# 06-Si5341_PLL.net
KiCad netlist of a schematic drawn in Altium Designer
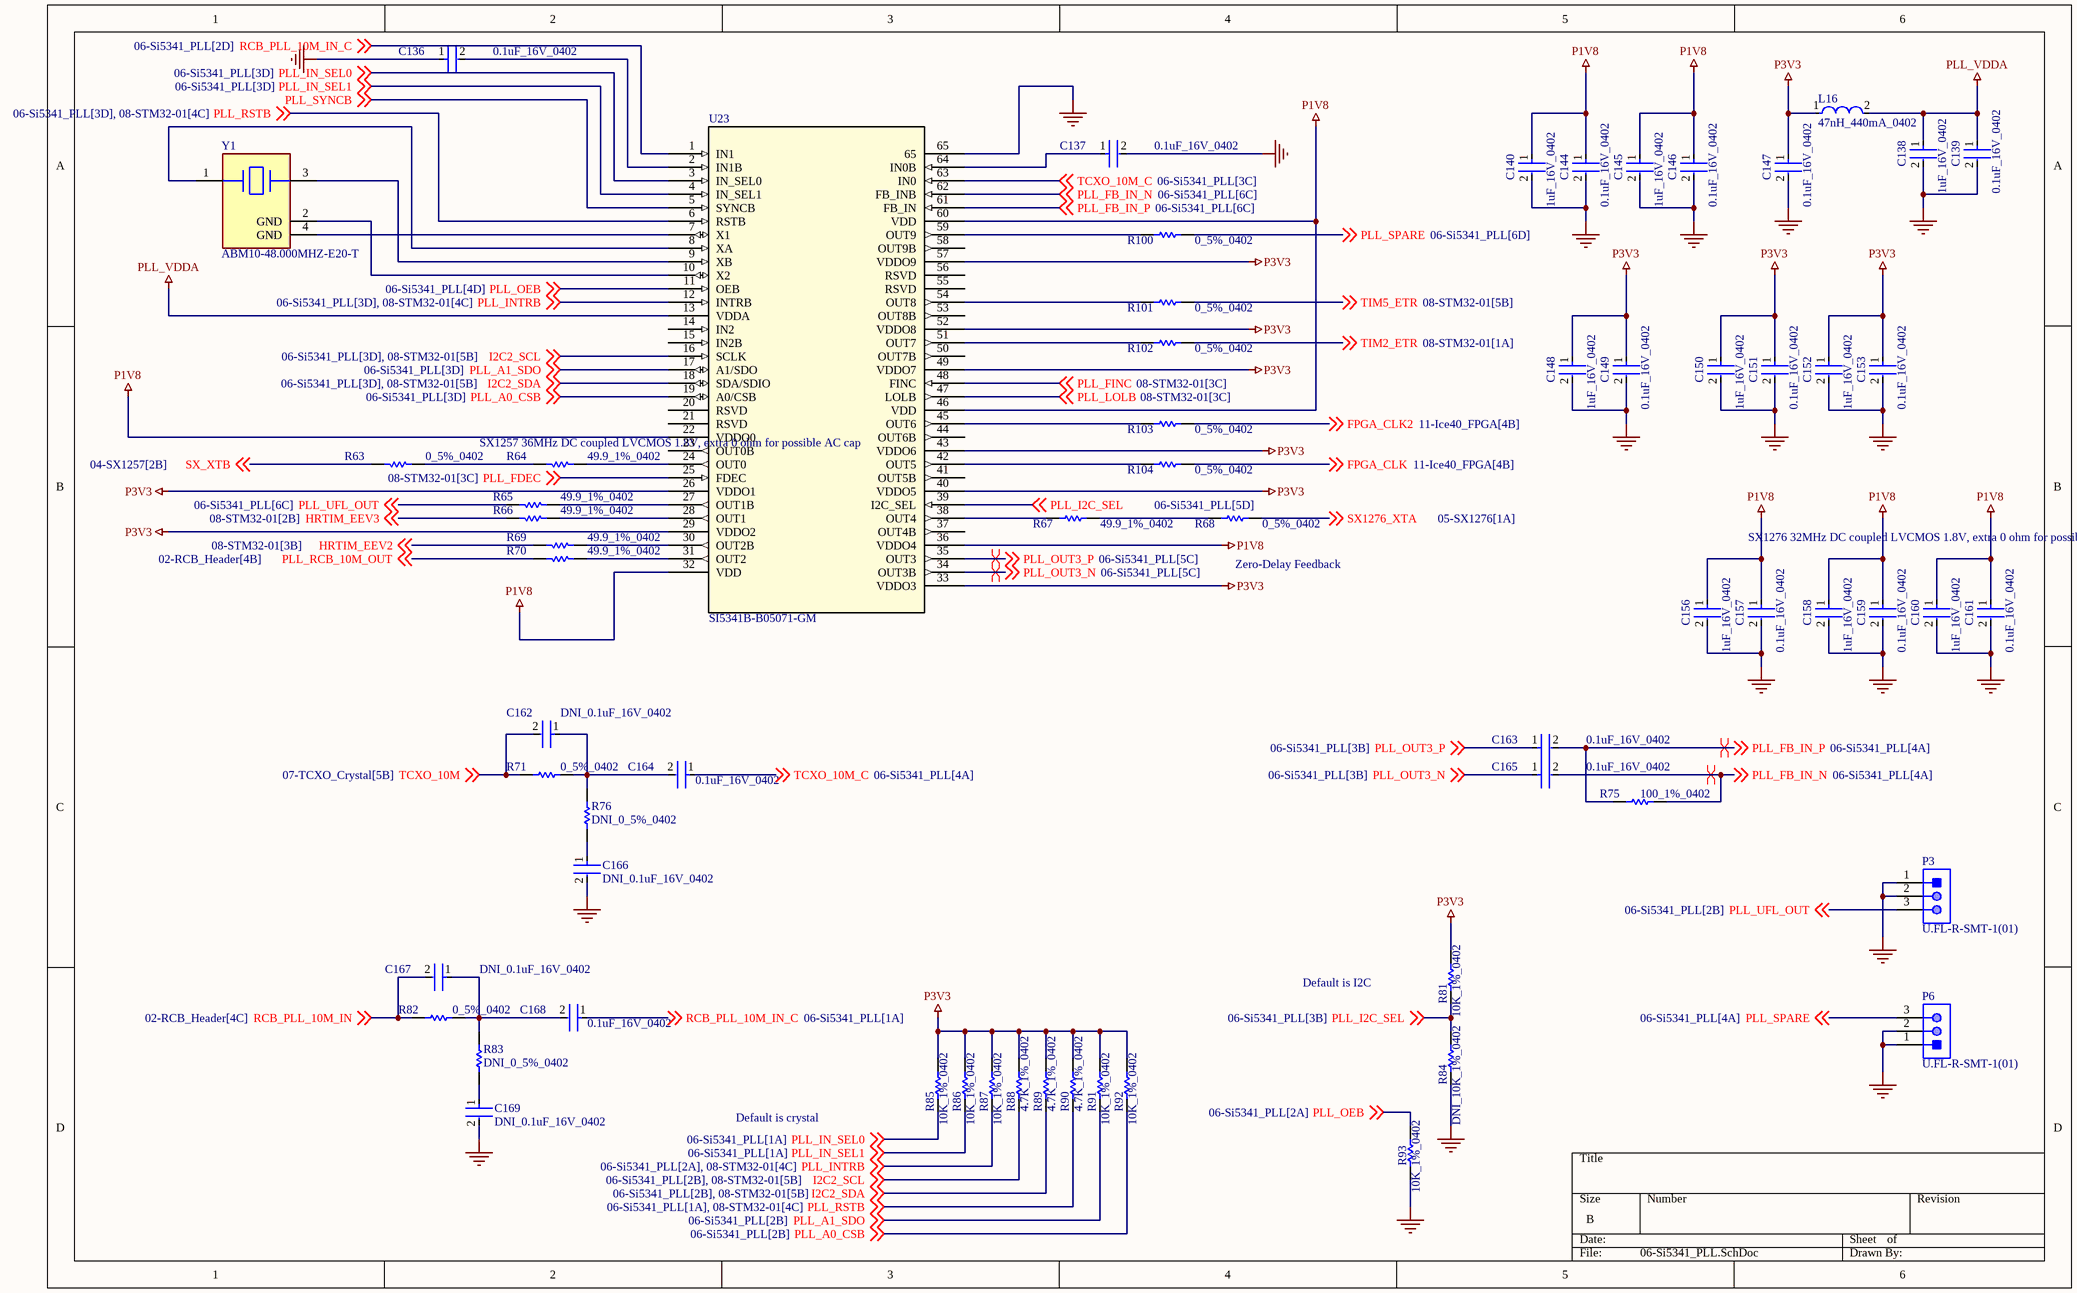
[diagram p0: 06-Si5341_PLL.SchDoc]

(export (version "E")
  (design (tool "Eeschema 10.0.6"))
  (components
    (comp (ref "C136")
      (value "0.1uF_16V_0402")
      (footprint "FP-C0402-BB-MFG")
      (description "CAP CER 0.1UF 16V 5% X7R 0402")
      (fields
        (field (name "MANUFACTURER") "Kemet")
        (field (name "MANUFACTURER PART NUMBER") "C0402C104J4RACTU")
      )
      (libsource (lib "Altium Content Vault") (part "b4654b650e69147ec39a6b967a45e02"))
    )
    (comp (ref "C137")
      (value "0.1uF_16V_0402")
      (footprint "FP-C0402-BB-MFG")
      (description "CAP CER 0.1UF 16V 5% X7R 0402")
      (fields
        (field (name "MANUFACTURER") "Kemet")
        (field (name "MANUFACTURER PART NUMBER") "C0402C104J4RACTU")
      )
      (libsource (lib "Altium Content Vault") (part "b4654b650e69147ec39a6b967a45e02"))
    )
    (comp (ref "C138")
      (value "1uF_16V_0402")
      (footprint "FP-0402-L_1_0_0_05-W_0_5-IPC_A")
      (description "None")
      (fields (field (name "TOLERANCE") "10%"))
      (libsource (lib "Altium Content Vault") (part "b4654b650e69147ec39a6b967a45e02"))
    )
    (comp (ref "C139")
      (value "0.1uF_16V_0402")
      (footprint "FP-C0402-BB-MFG")
      (description "CAP CER 0.1UF 16V 5% X7R 0402")
      (fields
        (field (name "MANUFACTURER") "Kemet")
        (field (name "MANUFACTURER PART NUMBER") "C0402C104J4RACTU")
      )
      (libsource (lib "Altium Content Vault") (part "b4654b650e69147ec39a6b967a45e02"))
    )
    (comp (ref "C140")
      (value "1uF_16V_0402")
      (footprint "FP-0402-L_1_0_0_05-W_0_5-IPC_A")
      (description "None")
      (fields (field (name "TOLERANCE") "10%"))
      (libsource (lib "Altium Content Vault") (part "b4654b650e69147ec39a6b967a45e02"))
    )
    (comp (ref "C144")
      (value "0.1uF_16V_0402")
      (footprint "FP-C0402-BB-MFG")
      (description "CAP CER 0.1UF 16V 5% X7R 0402")
      (fields
        (field (name "MANUFACTURER") "Kemet")
        (field (name "MANUFACTURER PART NUMBER") "C0402C104J4RACTU")
      )
      (libsource (lib "Altium Content Vault") (part "b4654b650e69147ec39a6b967a45e02"))
    )
    (comp (ref "C145")
      (value "1uF_16V_0402")
      (footprint "FP-0402-L_1_0_0_05-W_0_5-IPC_A")
      (description "None")
      (fields (field (name "TOLERANCE") "10%"))
      (libsource (lib "Altium Content Vault") (part "b4654b650e69147ec39a6b967a45e02"))
    )
    (comp (ref "C146")
      (value "0.1uF_16V_0402")
      (footprint "FP-C0402-BB-MFG")
      (description "CAP CER 0.1UF 16V 5% X7R 0402")
      (fields
        (field (name "MANUFACTURER") "Kemet")
        (field (name "MANUFACTURER PART NUMBER") "C0402C104J4RACTU")
      )
      (libsource (lib "Altium Content Vault") (part "b4654b650e69147ec39a6b967a45e02"))
    )
    (comp (ref "C147")
      (value "0.1uF_16V_0402")
      (footprint "FP-C0402-BB-MFG")
      (description "CAP CER 0.1UF 16V 5% X7R 0402")
      (fields
        (field (name "MANUFACTURER") "Kemet")
        (field (name "MANUFACTURER PART NUMBER") "C0402C104J4RACTU")
      )
      (libsource (lib "Altium Content Vault") (part "b4654b650e69147ec39a6b967a45e02"))
    )
    (comp (ref "C148")
      (value "1uF_16V_0402")
      (footprint "FP-0402-L_1_0_0_05-W_0_5-IPC_A")
      (description "None")
      (fields (field (name "TOLERANCE") "10%"))
      (libsource (lib "Altium Content Vault") (part "b4654b650e69147ec39a6b967a45e02"))
    )
    (comp (ref "C149")
      (value "0.1uF_16V_0402")
      (footprint "FP-C0402-BB-MFG")
      (description "CAP CER 0.1UF 16V 5% X7R 0402")
      (fields
        (field (name "MANUFACTURER") "Kemet")
        (field (name "MANUFACTURER PART NUMBER") "C0402C104J4RACTU")
      )
      (libsource (lib "Altium Content Vault") (part "b4654b650e69147ec39a6b967a45e02"))
    )
    (comp (ref "C150")
      (value "1uF_16V_0402")
      (footprint "FP-0402-L_1_0_0_05-W_0_5-IPC_A")
      (description "None")
      (fields (field (name "TOLERANCE") "10%"))
      (libsource (lib "Altium Content Vault") (part "b4654b650e69147ec39a6b967a45e02"))
    )
    (comp (ref "C151")
      (value "0.1uF_16V_0402")
      (footprint "FP-C0402-BB-MFG")
      (description "CAP CER 0.1UF 16V 5% X7R 0402")
      (fields
        (field (name "MANUFACTURER") "Kemet")
        (field (name "MANUFACTURER PART NUMBER") "C0402C104J4RACTU")
      )
      (libsource (lib "Altium Content Vault") (part "b4654b650e69147ec39a6b967a45e02"))
    )
    (comp (ref "C152")
      (value "1uF_16V_0402")
      (footprint "FP-0402-L_1_0_0_05-W_0_5-IPC_A")
      (description "None")
      (fields (field (name "TOLERANCE") "10%"))
      (libsource (lib "Altium Content Vault") (part "b4654b650e69147ec39a6b967a45e02"))
    )
    (comp (ref "C153")
      (value "0.1uF_16V_0402")
      (footprint "FP-C0402-BB-MFG")
      (description "CAP CER 0.1UF 16V 5% X7R 0402")
      (fields
        (field (name "MANUFACTURER") "Kemet")
        (field (name "MANUFACTURER PART NUMBER") "C0402C104J4RACTU")
      )
      (libsource (lib "Altium Content Vault") (part "b4654b650e69147ec39a6b967a45e02"))
    )
    (comp (ref "C156")
      (value "1uF_16V_0402")
      (footprint "FP-0402-L_1_0_0_05-W_0_5-IPC_A")
      (description "None")
      (fields (field (name "TOLERANCE") "10%"))
      (libsource (lib "Altium Content Vault") (part "b4654b650e69147ec39a6b967a45e02"))
    )
    (comp (ref "C157")
      (value "0.1uF_16V_0402")
      (footprint "FP-C0402-BB-MFG")
      (description "CAP CER 0.1UF 16V 5% X7R 0402")
      (fields
        (field (name "MANUFACTURER") "Kemet")
        (field (name "MANUFACTURER PART NUMBER") "C0402C104J4RACTU")
      )
      (libsource (lib "Altium Content Vault") (part "b4654b650e69147ec39a6b967a45e02"))
    )
    (comp (ref "C158")
      (value "1uF_16V_0402")
      (footprint "FP-0402-L_1_0_0_05-W_0_5-IPC_A")
      (description "None")
      (fields (field (name "TOLERANCE") "10%"))
      (libsource (lib "Altium Content Vault") (part "b4654b650e69147ec39a6b967a45e02"))
    )
    (comp (ref "C159")
      (value "0.1uF_16V_0402")
      (footprint "FP-C0402-BB-MFG")
      (description "CAP CER 0.1UF 16V 5% X7R 0402")
      (fields
        (field (name "MANUFACTURER") "Kemet")
        (field (name "MANUFACTURER PART NUMBER") "C0402C104J4RACTU")
      )
      (libsource (lib "Altium Content Vault") (part "b4654b650e69147ec39a6b967a45e02"))
    )
    (comp (ref "C160")
      (value "1uF_16V_0402")
      (footprint "FP-0402-L_1_0_0_05-W_0_5-IPC_A")
      (description "None")
      (fields (field (name "TOLERANCE") "10%"))
      (libsource (lib "Altium Content Vault") (part "b4654b650e69147ec39a6b967a45e02"))
    )
    (comp (ref "C161")
      (value "0.1uF_16V_0402")
      (footprint "FP-C0402-BB-MFG")
      (description "CAP CER 0.1UF 16V 5% X7R 0402")
      (fields
        (field (name "MANUFACTURER") "Kemet")
        (field (name "MANUFACTURER PART NUMBER") "C0402C104J4RACTU")
      )
      (libsource (lib "Altium Content Vault") (part "b4654b650e69147ec39a6b967a45e02"))
    )
    (comp (ref "C162")
      (value "DNI_0.1uF_16V_0402")
      (footprint "FP-C0402-BB-MFG")
      (description "CAP CER 0.1UF 16V 5% X7R 0402")
      (fields
        (field (name "MANUFACTURER") "Kemet")
        (field (name "MANUFACTURER PART NUMBER") "C0402C104J4RACTU")
      )
      (libsource (lib "Altium Content Vault") (part "b4654b650e69147ec39a6b967a45e02"))
    )
    (comp (ref "C163")
      (value "0.1uF_16V_0402")
      (footprint "FP-C0402-BB-MFG")
      (description "CAP CER 0.1UF 16V 5% X7R 0402")
      (fields
        (field (name "MANUFACTURER") "Kemet")
        (field (name "MANUFACTURER PART NUMBER") "C0402C104J4RACTU")
      )
      (libsource (lib "Altium Content Vault") (part "b4654b650e69147ec39a6b967a45e02"))
    )
    (comp (ref "C164")
      (value "0.1uF_16V_0402")
      (footprint "FP-C0402-BB-MFG")
      (description "CAP CER 0.1UF 16V 5% X7R 0402")
      (fields
        (field (name "MANUFACTURER") "Kemet")
        (field (name "MANUFACTURER PART NUMBER") "C0402C104J4RACTU")
      )
      (libsource (lib "Altium Content Vault") (part "b4654b650e69147ec39a6b967a45e02"))
    )
    (comp (ref "C165")
      (value "0.1uF_16V_0402")
      (footprint "FP-C0402-BB-MFG")
      (description "CAP CER 0.1UF 16V 5% X7R 0402")
      (fields
        (field (name "MANUFACTURER") "Kemet")
        (field (name "MANUFACTURER PART NUMBER") "C0402C104J4RACTU")
      )
      (libsource (lib "Altium Content Vault") (part "b4654b650e69147ec39a6b967a45e02"))
    )
    (comp (ref "C166")
      (value "DNI_0.1uF_16V_0402")
      (footprint "FP-C0402-BB-MFG")
      (description "CAP CER 0.1UF 16V 5% X7R 0402")
      (fields
        (field (name "MANUFACTURER") "Kemet")
        (field (name "MANUFACTURER PART NUMBER") "C0402C104J4RACTU")
      )
      (libsource (lib "Altium Content Vault") (part "b4654b650e69147ec39a6b967a45e02"))
    )
    (comp (ref "C167")
      (value "DNI_0.1uF_16V_0402")
      (footprint "FP-C0402-BB-MFG")
      (description "CAP CER 0.1UF 16V 5% X7R 0402")
      (fields
        (field (name "MANUFACTURER") "Kemet")
        (field (name "MANUFACTURER PART NUMBER") "C0402C104J4RACTU")
      )
      (libsource (lib "Altium Content Vault") (part "b4654b650e69147ec39a6b967a45e02"))
    )
    (comp (ref "C168")
      (value "0.1uF_16V_0402")
      (footprint "FP-C0402-BB-MFG")
      (description "CAP CER 0.1UF 16V 5% X7R 0402")
      (fields
        (field (name "MANUFACTURER") "Kemet")
        (field (name "MANUFACTURER PART NUMBER") "C0402C104J4RACTU")
      )
      (libsource (lib "Altium Content Vault") (part "b4654b650e69147ec39a6b967a45e02"))
    )
    (comp (ref "C169")
      (value "DNI_0.1uF_16V_0402")
      (footprint "FP-C0402-BB-MFG")
      (description "CAP CER 0.1UF 16V 5% X7R 0402")
      (fields
        (field (name "MANUFACTURER") "Kemet")
        (field (name "MANUFACTURER PART NUMBER") "C0402C104J4RACTU")
      )
      (libsource (lib "Altium Content Vault") (part "b4654b650e69147ec39a6b967a45e02"))
    )
    (comp (ref "L16")
      (value "47nH_440mA_0402")
      (footprint "FP-LQW15AN_80-MFG")
      (description "Wire Wound RF Inductor 47nH ±5% 440mA 0.648Ω 0402 (1005)")
      (fields (field (name "TOLERANCE") "5%"))
      (libsource (lib "Altium Content Vault") (part "725321dda6339637d4d059423bc1c3c"))
    )
    (comp (ref "P3")
      (value "U.FL-R-SMT-1(01)")
      (footprint "HRS-U.FL-R-SMT-3_V")
      (description "Ultra Small Coaxial Connector, 6 GHz, -40 to 90 degC, 3-Pin SMD, RoHS, Bulk")
      (fields (field (name "MANUFACTURER") "Hirose Electric"))
      (libsource (lib "Altium Content Vault") (part "CN-1P-M-R3"))
    )
    (comp (ref "P6")
      (value "U.FL-R-SMT-1(01)")
      (footprint "HRS-U.FL-R-SMT-3_V")
      (description "Ultra Small Coaxial Connector, 6 GHz, -40 to 90 degC, 3-Pin SMD, RoHS, Bulk")
      (fields (field (name "MANUFACTURER") "Hirose Electric"))
      (libsource (lib "") (part "CN-1P-M-R3_1"))
    )
    (comp (ref "R63")
      (value "0_5%_0402")
      (footprint "RESC1005X40X25NL05T10")
      (fields (field (name "MANUFACTURER") "Panasonic") (field (name "PART NUMBER") "ERJ-U020R00X"))
      (libsource (lib "Altium Content Vault") (part "RES"))
    )
    (comp (ref "R64")
      (value "49.9_1%_0402")
      (footprint "RESC1005X40X25NL10T10")
      (fields (field (name "PART NUMBER") "RK73H1ETTP49R9F") (field (name "MANUFACTURER") "KOA Speer"))
      (libsource (lib "Altium Content Vault") (part "RES"))
    )
    (comp (ref "R65")
      (value "49.9_1%_0402")
      (footprint "RESC1005X40X25NL10T10")
      (fields (field (name "PART NUMBER") "RK73H1ETTP49R9F") (field (name "MANUFACTURER") "KOA Speer"))
      (libsource (lib "Altium Content Vault") (part "RES"))
    )
    (comp (ref "R66")
      (value "49.9_1%_0402")
      (footprint "RESC1005X40X25NL10T10")
      (fields (field (name "PART NUMBER") "RK73H1ETTP49R9F") (field (name "MANUFACTURER") "KOA Speer"))
      (libsource (lib "Altium Content Vault") (part "RES"))
    )
    (comp (ref "R67")
      (value "49.9_1%_0402")
      (footprint "RESC1005X40X25NL10T10")
      (fields (field (name "PART NUMBER") "RK73H1ETTP49R9F") (field (name "MANUFACTURER") "KOA Speer"))
      (libsource (lib "Altium Content Vault") (part "RES"))
    )
    (comp (ref "R68")
      (value "0_5%_0402")
      (footprint "RESC1005X40X25NL05T10")
      (fields (field (name "MANUFACTURER") "Panasonic") (field (name "PART NUMBER") "ERJ-U020R00X"))
      (libsource (lib "Altium Content Vault") (part "RES"))
    )
    (comp (ref "R69")
      (value "49.9_1%_0402")
      (footprint "RESC1005X40X25NL10T10")
      (fields (field (name "PART NUMBER") "RK73H1ETTP49R9F") (field (name "MANUFACTURER") "KOA Speer"))
      (libsource (lib "Altium Content Vault") (part "RES"))
    )
    (comp (ref "R70")
      (value "49.9_1%_0402")
      (footprint "RESC1005X40X25NL10T10")
      (fields (field (name "PART NUMBER") "RK73H1ETTP49R9F") (field (name "MANUFACTURER") "KOA Speer"))
      (libsource (lib "Altium Content Vault") (part "RES"))
    )
    (comp (ref "R71")
      (value "0_5%_0402")
      (footprint "RESC1005X40X25NL05T10")
      (fields (field (name "MANUFACTURER") "Panasonic") (field (name "PART NUMBER") "ERJ-U020R00X"))
      (libsource (lib "Altium Content Vault") (part "RES"))
    )
    (comp (ref "R75")
      (value "100_1%_0402")
      (footprint "RESC1005X40X25NL05T10")
      (fields (field (name "MANUFACTURER") "Yageo") (field (name "PART NUMBER") "RC0402FR-13100RL"))
      (libsource (lib "Altium Content Vault") (part "RES"))
    )
    (comp (ref "R76")
      (value "DNI_0_5%_0402")
      (footprint "RESC1005X40X25NL05T10")
      (fields (field (name "MANUFACTURER") "Panasonic") (field (name "PART NUMBER") "ERJ-U020R00X"))
      (libsource (lib "Altium Content Vault") (part "RES"))
    )
    (comp (ref "R81")
      (value "10K_1%_0402")
      (footprint "RESC1005X40X25NL10T10")
      (fields (field (name "MANUFACTURER") "Bourns") (field (name "PART NUMBER") "CR0402-FX-1002GLF"))
      (libsource (lib "Altium Content Vault") (part "RES"))
    )
    (comp (ref "R82")
      (value "0_5%_0402")
      (footprint "RESC1005X40X25NL05T10")
      (fields (field (name "MANUFACTURER") "Panasonic") (field (name "PART NUMBER") "ERJ-U020R00X"))
      (libsource (lib "Altium Content Vault") (part "RES"))
    )
    (comp (ref "R83")
      (value "DNI_0_5%_0402")
      (footprint "RESC1005X40X25NL05T10")
      (fields (field (name "MANUFACTURER") "Panasonic") (field (name "PART NUMBER") "ERJ-U020R00X"))
      (libsource (lib "Altium Content Vault") (part "RES"))
    )
    (comp (ref "R84")
      (value "DNI_10K_1%_0402")
      (footprint "RESC1005X40X25NL10T10")
      (fields (field (name "MANUFACTURER") "Bourns") (field (name "PART NUMBER") "CR0402-FX-1002GLF"))
      (libsource (lib "Altium Content Vault") (part "RES"))
    )
    (comp (ref "R85")
      (value "10K_1%_0402")
      (footprint "RESC1005X40X25NL10T10")
      (fields (field (name "MANUFACTURER") "Bourns") (field (name "PART NUMBER") "CR0402-FX-1002GLF"))
      (libsource (lib "Altium Content Vault") (part "RES"))
    )
    (comp (ref "R86")
      (value "10K_1%_0402")
      (footprint "RESC1005X40X25NL10T10")
      (fields (field (name "MANUFACTURER") "Bourns") (field (name "PART NUMBER") "CR0402-FX-1002GLF"))
      (libsource (lib "Altium Content Vault") (part "RES"))
    )
    (comp (ref "R87")
      (value "10K_1%_0402")
      (footprint "RESC1005X40X25NL10T10")
      (fields (field (name "MANUFACTURER") "Bourns") (field (name "PART NUMBER") "CR0402-FX-1002GLF"))
      (libsource (lib "Altium Content Vault") (part "RES"))
    )
    (comp (ref "R88")
      (value "4.7K_1%_0402")
      (footprint "RESC1005X40X25NL10T10")
      (fields (field (name "MANUFACTURER") "Bourns") (field (name "PART NUMBER") "CR0402-FX-4701GLF"))
      (libsource (lib "Altium Content Vault") (part "RES"))
    )
    (comp (ref "R89")
      (value "4.7K_1%_0402")
      (footprint "RESC1005X40X25NL10T10")
      (fields (field (name "MANUFACTURER") "Bourns") (field (name "PART NUMBER") "CR0402-FX-4701GLF"))
      (libsource (lib "Altium Content Vault") (part "RES"))
    )
    (comp (ref "R90")
      (value "4.7K_1%_0402")
      (footprint "RESC1005X40X25NL10T10")
      (fields (field (name "MANUFACTURER") "Bourns") (field (name "PART NUMBER") "CR0402-FX-4701GLF"))
      (libsource (lib "Altium Content Vault") (part "RES"))
    )
    (comp (ref "R91")
      (value "10K_1%_0402")
      (footprint "RESC1005X40X25NL10T10")
      (fields (field (name "MANUFACTURER") "Bourns") (field (name "PART NUMBER") "CR0402-FX-1002GLF"))
      (libsource (lib "Altium Content Vault") (part "RES"))
    )
    (comp (ref "R92")
      (value "10K_1%_0402")
      (footprint "RESC1005X40X25NL10T10")
      (fields (field (name "MANUFACTURER") "Bourns") (field (name "PART NUMBER") "CR0402-FX-1002GLF"))
      (libsource (lib "Altium Content Vault") (part "RES"))
    )
    (comp (ref "R93")
      (value "10K_1%_0402")
      (footprint "RESC1005X40X25NL10T10")
      (fields (field (name "MANUFACTURER") "Bourns") (field (name "PART NUMBER") "CR0402-FX-1002GLF"))
      (libsource (lib "Altium Content Vault") (part "RES"))
    )
    (comp (ref "R100")
      (value "0_5%_0402")
      (footprint "RESC1005X40X25NL05T10")
      (fields (field (name "MANUFACTURER") "Panasonic") (field (name "PART NUMBER") "ERJ-U020R00X"))
      (libsource (lib "Altium Content Vault") (part "RES"))
    )
    (comp (ref "R101")
      (value "0_5%_0402")
      (footprint "RESC1005X40X25NL05T10")
      (fields (field (name "MANUFACTURER") "Panasonic") (field (name "PART NUMBER") "ERJ-U020R00X"))
      (libsource (lib "Altium Content Vault") (part "RES"))
    )
    (comp (ref "R102")
      (value "0_5%_0402")
      (footprint "RESC1005X40X25NL05T10")
      (fields (field (name "MANUFACTURER") "Panasonic") (field (name "PART NUMBER") "ERJ-U020R00X"))
      (libsource (lib "Altium Content Vault") (part "RES"))
    )
    (comp (ref "R103")
      (value "0_5%_0402")
      (footprint "RESC1005X40X25NL05T10")
      (fields (field (name "MANUFACTURER") "Panasonic") (field (name "PART NUMBER") "ERJ-U020R00X"))
      (libsource (lib "Altium Content Vault") (part "RES"))
    )
    (comp (ref "R104")
      (value "0_5%_0402")
      (footprint "RESC1005X40X25NL05T10")
      (fields (field (name "MANUFACTURER") "Panasonic") (field (name "PART NUMBER") "ERJ-U020R00X"))
      (libsource (lib "Altium Content Vault") (part "RES"))
    )
    (comp (ref "U23")
      (value "SI5341B-B05071-GM")
      (footprint "QFN64_SI5341_SIL_SKY")
      (description "No Description Available")
      (fields (field (name "COPYRIGHT") "Copyright (C) 2023 Ultra Librarian. All rights reserved."))
      (libsource (lib "SI5341B-B05071-GM") (part "SI5341B-B05071-GM"))
    )
    (comp (ref "Y1")
      (value "ABM10-48.000MHZ-E20-T")
      (footprint "FP-ABM10-MFG")
      (description "Crystal 48MHz ±20ppm 10pF SMD-4 2.5mm x 2mm")
      (fields (field (name "TOLERANCE") "20ppm"))
      (libsource (lib "Altium Content Vault") (part "0934ba461506c7e3a0bb4df7a4ed385"))
    )
  )
  (nets
    (net (code "1") (name "FPGA_CLK") (class "Default")
      (node (ref "R104") (pin "2") (pinfunction "2_2") (pintype "passive"))
    )
    (net (code "2") (name "FPGA_CLK2") (class "Default")
      (node (ref "R103") (pin "2") (pinfunction "2_2") (pintype "passive"))
    )
    (net (code "3") (name "GND") (class "Default")
      (node (ref "C136") (pin "1") (pinfunction "1_1") (pintype "passive"))
      (node (ref "C137") (pin "2") (pinfunction "2_2") (pintype "passive"))
      (node (ref "C138") (pin "2") (pinfunction "2_2") (pintype "passive"))
      (node (ref "C139") (pin "2") (pinfunction "2_2") (pintype "passive"))
      (node (ref "C140") (pin "2") (pinfunction "2_2") (pintype "passive"))
      (node (ref "C144") (pin "2") (pinfunction "2_2") (pintype "passive"))
      (node (ref "C145") (pin "2") (pinfunction "2_2") (pintype "passive"))
      (node (ref "C146") (pin "2") (pinfunction "2_2") (pintype "passive"))
      (node (ref "C147") (pin "2") (pinfunction "2_2") (pintype "passive"))
      (node (ref "C148") (pin "2") (pinfunction "2_2") (pintype "passive"))
      (node (ref "C149") (pin "2") (pinfunction "2_2") (pintype "passive"))
      (node (ref "C150") (pin "2") (pinfunction "2_2") (pintype "passive"))
      (node (ref "C151") (pin "2") (pinfunction "2_2") (pintype "passive"))
      (node (ref "C152") (pin "2") (pinfunction "2_2") (pintype "passive"))
      (node (ref "C153") (pin "2") (pinfunction "2_2") (pintype "passive"))
      (node (ref "C156") (pin "2") (pinfunction "2_2") (pintype "passive"))
      (node (ref "C157") (pin "2") (pinfunction "2_2") (pintype "passive"))
      (node (ref "C158") (pin "2") (pinfunction "2_2") (pintype "passive"))
      (node (ref "C159") (pin "2") (pinfunction "2_2") (pintype "passive"))
      (node (ref "C160") (pin "2") (pinfunction "2_2") (pintype "passive"))
      (node (ref "C161") (pin "2") (pinfunction "2_2") (pintype "passive"))
      (node (ref "C166") (pin "2") (pinfunction "2_2") (pintype "passive"))
      (node (ref "C169") (pin "2") (pinfunction "2_2") (pintype "passive"))
      (node (ref "P3") (pin "1") (pinfunction "1_1") (pintype "passive"))
      (node (ref "P3") (pin "2") (pinfunction "2_2") (pintype "passive"))
      (node (ref "P6") (pin "1") (pinfunction "1_1") (pintype "passive"))
      (node (ref "P6") (pin "2") (pinfunction "2_2") (pintype "passive"))
      (node (ref "R84") (pin "1") (pinfunction "1_1") (pintype "passive"))
      (node (ref "R93") (pin "1") (pinfunction "1_1") (pintype "passive"))
      (node (ref "U23") (pin "65") (pinfunction "65_65") (pintype "passive"))
    )
    (net (code "4") (name "HRTIM_EEV2") (class "Default")
      (node (ref "R69") (pin "1") (pinfunction "1_1") (pintype "passive"))
    )
    (net (code "5") (name "HRTIM_EEV3") (class "Default")
      (node (ref "R66") (pin "1") (pinfunction "1_1") (pintype "passive"))
    )
    (net (code "6") (name "I2C2_SCL") (class "Default")
      (node (ref "R88") (pin "1") (pinfunction "1_1") (pintype "passive"))
      (node (ref "U23") (pin "16") (pinfunction "SCLK_16") (pintype "input"))
    )
    (net (code "7") (name "I2C2_SDA") (class "Default")
      (node (ref "R89") (pin "1") (pinfunction "1_1") (pintype "passive"))
      (node (ref "U23") (pin "18") (pinfunction "SDA/SDIO_18") (pintype "bidirectional"))
    )
    (net (code "8") (name "Net-(C162-Pad1)") (class "Default")
      (node (ref "C162") (pin "1") (pinfunction "1_1") (pintype "passive"))
      (node (ref "C164") (pin "2") (pinfunction "2_2") (pintype "passive"))
      (node (ref "R71") (pin "2") (pinfunction "2_2") (pintype "passive"))
      (node (ref "R76") (pin "2") (pinfunction "2_2") (pintype "passive"))
    )
    (net (code "9") (name "Net-(C166-Pad1)") (class "Default")
      (node (ref "C166") (pin "1") (pinfunction "1_1") (pintype "passive"))
      (node (ref "R76") (pin "1") (pinfunction "1_1") (pintype "passive"))
    )
    (net (code "10") (name "Net-(C167-Pad1)") (class "Default")
      (node (ref "C167") (pin "1") (pinfunction "1_1") (pintype "passive"))
      (node (ref "C168") (pin "2") (pinfunction "2_2") (pintype "passive"))
      (node (ref "R82") (pin "2") (pinfunction "2_2") (pintype "passive"))
      (node (ref "R83") (pin "2") (pinfunction "2_2") (pintype "passive"))
    )
    (net (code "11") (name "Net-(C169-Pad1)") (class "Default")
      (node (ref "C169") (pin "1") (pinfunction "1_1") (pintype "passive"))
      (node (ref "R83") (pin "1") (pinfunction "1_1") (pintype "passive"))
    )
    (net (code "12") (name "Net-(R63-Pad1)") (class "Default")
      (node (ref "R63") (pin "1") (pinfunction "1_1") (pintype "passive"))
      (node (ref "R64") (pin "1") (pinfunction "1_1") (pintype "passive"))
    )
    (net (code "13") (name "Net-(R67-Pad1)") (class "Default")
      (node (ref "R67") (pin "1") (pinfunction "1_1") (pintype "passive"))
      (node (ref "R68") (pin "1") (pinfunction "1_1") (pintype "passive"))
    )
    (net (code "14") (name "Net-(U23-IN0B)") (class "Default")
      (node (ref "C137") (pin "1") (pinfunction "1_1") (pintype "passive"))
      (node (ref "U23") (pin "64") (pinfunction "IN0B_64") (pintype "input"))
    )
    (net (code "15") (name "Net-(U23-IN1B)") (class "Default")
      (node (ref "C136") (pin "2") (pinfunction "2_2") (pintype "passive"))
      (node (ref "U23") (pin "2") (pinfunction "IN1B_2") (pintype "input"))
    )
    (net (code "16") (name "Net-(U23-OUT0)") (class "Default")
      (node (ref "R64") (pin "2") (pinfunction "2_2") (pintype "passive"))
      (node (ref "U23") (pin "24") (pinfunction "OUT0_24") (pintype "output"))
    )
    (net (code "17") (name "Net-(U23-OUT1)") (class "Default")
      (node (ref "R66") (pin "2") (pinfunction "2_2") (pintype "passive"))
      (node (ref "U23") (pin "28") (pinfunction "OUT1_28") (pintype "output"))
    )
    (net (code "18") (name "Net-(U23-OUT1B)") (class "Default")
      (node (ref "R65") (pin "2") (pinfunction "2_2") (pintype "passive"))
      (node (ref "U23") (pin "27") (pinfunction "OUT1B_27") (pintype "output"))
    )
    (net (code "19") (name "Net-(U23-OUT2)") (class "Default")
      (node (ref "R70") (pin "2") (pinfunction "2_2") (pintype "passive"))
      (node (ref "U23") (pin "31") (pinfunction "OUT2_31") (pintype "output"))
    )
    (net (code "20") (name "Net-(U23-OUT2B)") (class "Default")
      (node (ref "R69") (pin "2") (pinfunction "2_2") (pintype "passive"))
      (node (ref "U23") (pin "30") (pinfunction "OUT2B_30") (pintype "output"))
    )
    (net (code "21") (name "Net-(U23-OUT4)") (class "Default")
      (node (ref "R67") (pin "2") (pinfunction "2_2") (pintype "passive"))
      (node (ref "U23") (pin "38") (pinfunction "OUT4_38") (pintype "output"))
    )
    (net (code "22") (name "Net-(U23-OUT5)") (class "Default")
      (node (ref "R104") (pin "1") (pinfunction "1_1") (pintype "passive"))
      (node (ref "U23") (pin "42") (pinfunction "OUT5_42") (pintype "output"))
    )
    (net (code "23") (name "Net-(U23-OUT6)") (class "Default")
      (node (ref "R103") (pin "1") (pinfunction "1_1") (pintype "passive"))
      (node (ref "U23") (pin "45") (pinfunction "OUT6_45") (pintype "output"))
    )
    (net (code "24") (name "Net-(U23-OUT7)") (class "Default")
      (node (ref "R102") (pin "1") (pinfunction "1_1") (pintype "passive"))
      (node (ref "U23") (pin "51") (pinfunction "OUT7_51") (pintype "output"))
    )
    (net (code "25") (name "Net-(U23-OUT8)") (class "Default")
      (node (ref "R101") (pin "1") (pinfunction "1_1") (pintype "passive"))
      (node (ref "U23") (pin "54") (pinfunction "OUT8_54") (pintype "output"))
    )
    (net (code "26") (name "Net-(U23-OUT9)") (class "Default")
      (node (ref "R100") (pin "1") (pinfunction "1_1") (pintype "passive"))
      (node (ref "U23") (pin "59") (pinfunction "OUT9_59") (pintype "output"))
    )
    (net (code "27") (name "Net-(U23-X1)") (class "Default")
      (node (ref "U23") (pin "7") (pinfunction "X1_7") (pintype "bidirectional"))
      (node (ref "Y1") (pin "4") (pinfunction "GND_4") (pintype "power_in"))
    )
    (net (code "28") (name "Net-(U23-X2)") (class "Default")
      (node (ref "U23") (pin "10") (pinfunction "X2_10") (pintype "bidirectional"))
      (node (ref "Y1") (pin "2") (pinfunction "GND_2") (pintype "power_in"))
    )
    (net (code "29") (name "Net-(U23-XA)") (class "Default")
      (node (ref "U23") (pin "8") (pinfunction "XA_8") (pintype "input"))
      (node (ref "Y1") (pin "1") (pinfunction "1_1") (pintype "passive"))
    )
    (net (code "30") (name "Net-(U23-XB)") (class "Default")
      (node (ref "U23") (pin "9") (pinfunction "XB_9") (pintype "input"))
      (node (ref "Y1") (pin "3") (pinfunction "3_3") (pintype "passive"))
    )
    (net (code "31") (name "P1V8") (class "Default")
      (node (ref "C140") (pin "1") (pinfunction "1_1") (pintype "passive"))
      (node (ref "C144") (pin "1") (pinfunction "1_1") (pintype "passive"))
      (node (ref "C145") (pin "1") (pinfunction "1_1") (pintype "passive"))
      (node (ref "C146") (pin "1") (pinfunction "1_1") (pintype "passive"))
      (node (ref "C156") (pin "1") (pinfunction "1_1") (pintype "passive"))
      (node (ref "C157") (pin "1") (pinfunction "1_1") (pintype "passive"))
      (node (ref "C158") (pin "1") (pinfunction "1_1") (pintype "passive"))
      (node (ref "C159") (pin "1") (pinfunction "1_1") (pintype "passive"))
      (node (ref "C160") (pin "1") (pinfunction "1_1") (pintype "passive"))
      (node (ref "C161") (pin "1") (pinfunction "1_1") (pintype "passive"))
      (node (ref "U23") (pin "22") (pinfunction "VDDO0_22") (pintype "power_in"))
      (node (ref "U23") (pin "32") (pinfunction "VDD_32") (pintype "power_in"))
      (node (ref "U23") (pin "36") (pinfunction "VDDO4_36") (pintype "power_in"))
      (node (ref "U23") (pin "46") (pinfunction "VDD_46") (pintype "power_in"))
      (node (ref "U23") (pin "60") (pinfunction "VDD_60") (pintype "power_in"))
    )
    (net (code "32") (name "P3V3") (class "Default")
      (node (ref "C147") (pin "1") (pinfunction "1_1") (pintype "passive"))
      (node (ref "C148") (pin "1") (pinfunction "1_1") (pintype "passive"))
      (node (ref "C149") (pin "1") (pinfunction "1_1") (pintype "passive"))
      (node (ref "C150") (pin "1") (pinfunction "1_1") (pintype "passive"))
      (node (ref "C151") (pin "1") (pinfunction "1_1") (pintype "passive"))
      (node (ref "C152") (pin "1") (pinfunction "1_1") (pintype "passive"))
      (node (ref "C153") (pin "1") (pinfunction "1_1") (pintype "passive"))
      (node (ref "L16") (pin "1") (pinfunction "1_1") (pintype "passive"))
      (node (ref "R81") (pin "2") (pinfunction "2_2") (pintype "passive"))
      (node (ref "R85") (pin "2") (pinfunction "2_2") (pintype "passive"))
      (node (ref "R86") (pin "2") (pinfunction "2_2") (pintype "passive"))
      (node (ref "R87") (pin "2") (pinfunction "2_2") (pintype "passive"))
      (node (ref "R88") (pin "2") (pinfunction "2_2") (pintype "passive"))
      (node (ref "R89") (pin "2") (pinfunction "2_2") (pintype "passive"))
      (node (ref "R90") (pin "2") (pinfunction "2_2") (pintype "passive"))
      (node (ref "R91") (pin "2") (pinfunction "2_2") (pintype "passive"))
      (node (ref "R92") (pin "2") (pinfunction "2_2") (pintype "passive"))
      (node (ref "U23") (pin "26") (pinfunction "VDDO1_26") (pintype "power_in"))
      (node (ref "U23") (pin "29") (pinfunction "VDDO2_29") (pintype "power_in"))
      (node (ref "U23") (pin "33") (pinfunction "VDDO3_33") (pintype "power_in"))
      (node (ref "U23") (pin "40") (pinfunction "VDDO5_40") (pintype "power_in"))
      (node (ref "U23") (pin "43") (pinfunction "VDDO6_43") (pintype "power_in"))
      (node (ref "U23") (pin "49") (pinfunction "VDDO7_49") (pintype "power_in"))
      (node (ref "U23") (pin "52") (pinfunction "VDDO8_52") (pintype "power_in"))
      (node (ref "U23") (pin "57") (pinfunction "VDDO9_57") (pintype "power_in"))
    )
    (net (code "33") (name "PLL_A0_CSB") (class "Default")
      (node (ref "R92") (pin "1") (pinfunction "1_1") (pintype "passive"))
      (node (ref "U23") (pin "19") (pinfunction "A0/CSB_19") (pintype "bidirectional"))
    )
    (net (code "34") (name "PLL_A1_SDO") (class "Default")
      (node (ref "R91") (pin "1") (pinfunction "1_1") (pintype "passive"))
      (node (ref "U23") (pin "17") (pinfunction "A1/SDO_17") (pintype "bidirectional"))
    )
    (net (code "35") (name "PLL_FB_IN_N") (class "Default")
      (node (ref "C165") (pin "2") (pinfunction "2_2") (pintype "passive"))
      (node (ref "R75") (pin "2") (pinfunction "2_2") (pintype "passive"))
      (node (ref "U23") (pin "62") (pinfunction "FB_INB_62") (pintype "input"))
    )
    (net (code "36") (name "PLL_FB_IN_P") (class "Default")
      (node (ref "C163") (pin "2") (pinfunction "2_2") (pintype "passive"))
      (node (ref "R75") (pin "1") (pinfunction "1_1") (pintype "passive"))
      (node (ref "U23") (pin "61") (pinfunction "FB_IN_61") (pintype "input"))
    )
    (net (code "37") (name "PLL_FDEC") (class "Default")
      (node (ref "U23") (pin "25") (pinfunction "FDEC_25") (pintype "input"))
    )
    (net (code "38") (name "PLL_FINC") (class "Default")
      (node (ref "U23") (pin "48") (pinfunction "FINC_48") (pintype "input"))
    )
    (net (code "39") (name "PLL_I2C_SEL") (class "Default")
      (node (ref "R81") (pin "1") (pinfunction "1_1") (pintype "passive"))
      (node (ref "R84") (pin "2") (pinfunction "2_2") (pintype "passive"))
      (node (ref "U23") (pin "39") (pinfunction "I2C_SEL_39") (pintype "input"))
    )
    (net (code "40") (name "PLL_INTRB") (class "Default")
      (node (ref "R87") (pin "1") (pinfunction "1_1") (pintype "passive"))
      (node (ref "U23") (pin "12") (pinfunction "INTRB_12") (pintype "input"))
    )
    (net (code "41") (name "PLL_IN_SEL0") (class "Default")
      (node (ref "R85") (pin "1") (pinfunction "1_1") (pintype "passive"))
      (node (ref "U23") (pin "3") (pinfunction "IN_SEL0_3") (pintype "input"))
    )
    (net (code "42") (name "PLL_IN_SEL1") (class "Default")
      (node (ref "R86") (pin "1") (pinfunction "1_1") (pintype "passive"))
      (node (ref "U23") (pin "4") (pinfunction "IN_SEL1_4") (pintype "input"))
    )
    (net (code "43") (name "PLL_LOLB") (class "Default")
      (node (ref "U23") (pin "47") (pinfunction "LOLB_47") (pintype "output"))
    )
    (net (code "44") (name "PLL_OEB") (class "Default")
      (node (ref "R93") (pin "2") (pinfunction "2_2") (pintype "passive"))
      (node (ref "U23") (pin "11") (pinfunction "OEB_11") (pintype "input"))
    )
    (net (code "45") (name "PLL_OUT3_N") (class "Default")
      (node (ref "C165") (pin "1") (pinfunction "1_1") (pintype "passive"))
      (node (ref "U23") (pin "34") (pinfunction "OUT3B_34") (pintype "output"))
    )
    (net (code "46") (name "PLL_OUT3_P") (class "Default")
      (node (ref "C163") (pin "1") (pinfunction "1_1") (pintype "passive"))
      (node (ref "U23") (pin "35") (pinfunction "OUT3_35") (pintype "output"))
    )
    (net (code "47") (name "PLL_RCB_10M_OUT") (class "Default")
      (node (ref "R70") (pin "1") (pinfunction "1_1") (pintype "passive"))
    )
    (net (code "48") (name "PLL_RSTB") (class "Default")
      (node (ref "R90") (pin "1") (pinfunction "1_1") (pintype "passive"))
      (node (ref "U23") (pin "6") (pinfunction "RSTB_6") (pintype "input"))
    )
    (net (code "49") (name "PLL_SPARE") (class "Default")
      (node (ref "P6") (pin "3") (pinfunction "3_3") (pintype "passive"))
      (node (ref "R100") (pin "2") (pinfunction "2_2") (pintype "passive"))
    )
    (net (code "50") (name "PLL_SYNCB") (class "Default")
      (node (ref "U23") (pin "5") (pinfunction "SYNCB_5") (pintype "input"))
    )
    (net (code "51") (name "PLL_UFL_OUT") (class "Default")
      (node (ref "P3") (pin "3") (pinfunction "3_3") (pintype "passive"))
      (node (ref "R65") (pin "1") (pinfunction "1_1") (pintype "passive"))
    )
    (net (code "52") (name "PLL_VDDA") (class "Default")
      (node (ref "C138") (pin "1") (pinfunction "1_1") (pintype "passive"))
      (node (ref "C139") (pin "1") (pinfunction "1_1") (pintype "passive"))
      (node (ref "L16") (pin "2") (pinfunction "2_2") (pintype "passive"))
      (node (ref "U23") (pin "13") (pinfunction "VDDA_13") (pintype "power_in"))
    )
    (net (code "53") (name "RCB_PLL_10M_IN") (class "Default")
      (node (ref "C167") (pin "2") (pinfunction "2_2") (pintype "passive"))
      (node (ref "R82") (pin "1") (pinfunction "1_1") (pintype "passive"))
    )
    (net (code "54") (name "RCB_PLL_10M_IN_C") (class "Default")
      (node (ref "C168") (pin "1") (pinfunction "1_1") (pintype "passive"))
      (node (ref "U23") (pin "1") (pinfunction "IN1_1") (pintype "input"))
    )
    (net (code "55") (name "SX1276_XTA") (class "Default")
      (node (ref "R68") (pin "2") (pinfunction "2_2") (pintype "passive"))
    )
    (net (code "56") (name "SX_XTB") (class "Default")
      (node (ref "R63") (pin "2") (pinfunction "2_2") (pintype "passive"))
    )
    (net (code "57") (name "TCXO_10M") (class "Default")
      (node (ref "C162") (pin "2") (pinfunction "2_2") (pintype "passive"))
      (node (ref "R71") (pin "1") (pinfunction "1_1") (pintype "passive"))
    )
    (net (code "58") (name "TCXO_10M_C") (class "Default")
      (node (ref "C164") (pin "1") (pinfunction "1_1") (pintype "passive"))
      (node (ref "U23") (pin "63") (pinfunction "IN0_63") (pintype "input"))
    )
    (net (code "59") (name "TIM2_ETR") (class "Default")
      (node (ref "R102") (pin "2") (pinfunction "2_2") (pintype "passive"))
    )
    (net (code "60") (name "TIM5_ETR") (class "Default")
      (node (ref "R101") (pin "2") (pinfunction "2_2") (pintype "passive"))
    )
    (net (code "61") (name "unconnected-(U23-IN2-Pad14)") (class "Default")
      (node (ref "U23") (pin "14") (pinfunction "IN2_14") (pintype "input"))
    )
    (net (code "62") (name "unconnected-(U23-IN2B-Pad15)") (class "Default")
      (node (ref "U23") (pin "15") (pinfunction "IN2B_15") (pintype "input"))
    )
    (net (code "63") (name "unconnected-(U23-OUT0B-Pad23)") (class "Default")
      (node (ref "U23") (pin "23") (pinfunction "OUT0B_23") (pintype "output"))
    )
    (net (code "64") (name "unconnected-(U23-OUT4B-Pad37)") (class "Default")
      (node (ref "U23") (pin "37") (pinfunction "OUT4B_37") (pintype "output"))
    )
    (net (code "65") (name "unconnected-(U23-OUT5B-Pad41)") (class "Default")
      (node (ref "U23") (pin "41") (pinfunction "OUT5B_41") (pintype "output"))
    )
    (net (code "66") (name "unconnected-(U23-OUT6B-Pad44)") (class "Default")
      (node (ref "U23") (pin "44") (pinfunction "OUT6B_44") (pintype "output"))
    )
    (net (code "67") (name "unconnected-(U23-OUT7B-Pad50)") (class "Default")
      (node (ref "U23") (pin "50") (pinfunction "OUT7B_50") (pintype "output"))
    )
    (net (code "68") (name "unconnected-(U23-OUT8B-Pad53)") (class "Default")
      (node (ref "U23") (pin "53") (pinfunction "OUT8B_53") (pintype "output"))
    )
    (net (code "69") (name "unconnected-(U23-OUT9B-Pad58)") (class "Default")
      (node (ref "U23") (pin "58") (pinfunction "OUT9B_58") (pintype "output"))
    )
    (net (code "70") (name "unconnected-(U23-RSVD-Pad20)") (class "Default")
      (node (ref "U23") (pin "20") (pinfunction "RSVD_20") (pintype "passive"))
    )
    (net (code "71") (name "unconnected-(U23-RSVD-Pad21)") (class "Default")
      (node (ref "U23") (pin "21") (pinfunction "RSVD_21") (pintype "passive"))
    )
    (net (code "72") (name "unconnected-(U23-RSVD-Pad55)") (class "Default")
      (node (ref "U23") (pin "55") (pinfunction "RSVD_55") (pintype "passive"))
    )
    (net (code "73") (name "unconnected-(U23-RSVD-Pad56)") (class "Default")
      (node (ref "U23") (pin "56") (pinfunction "RSVD_56") (pintype "passive"))
    )
  )
)
